# PCB_Design.net
KiCad netlist of a schematic drawn in EAGLE
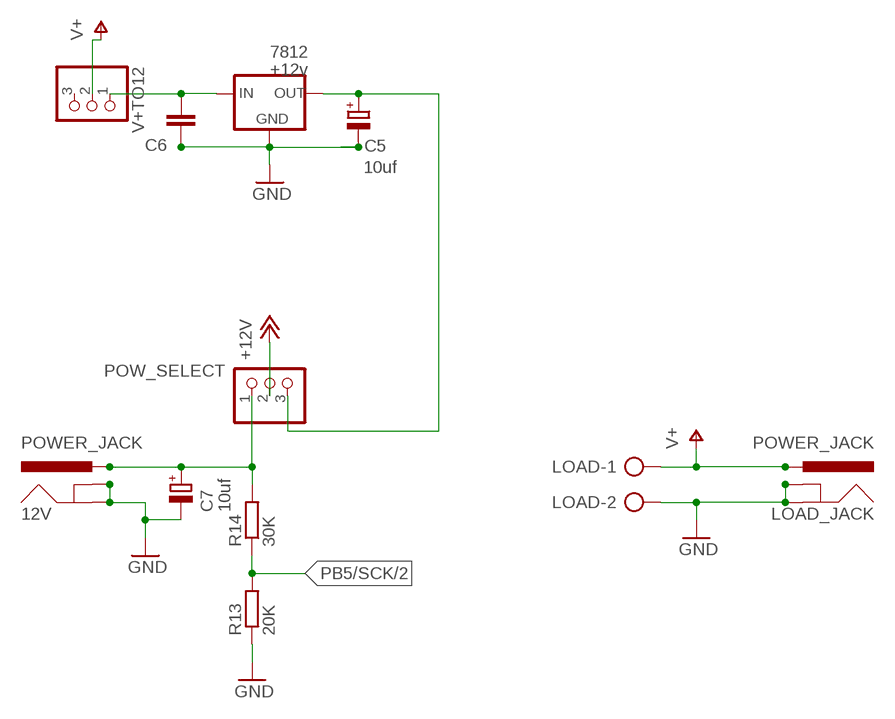
[diagram p0: schematic, sheet 1]
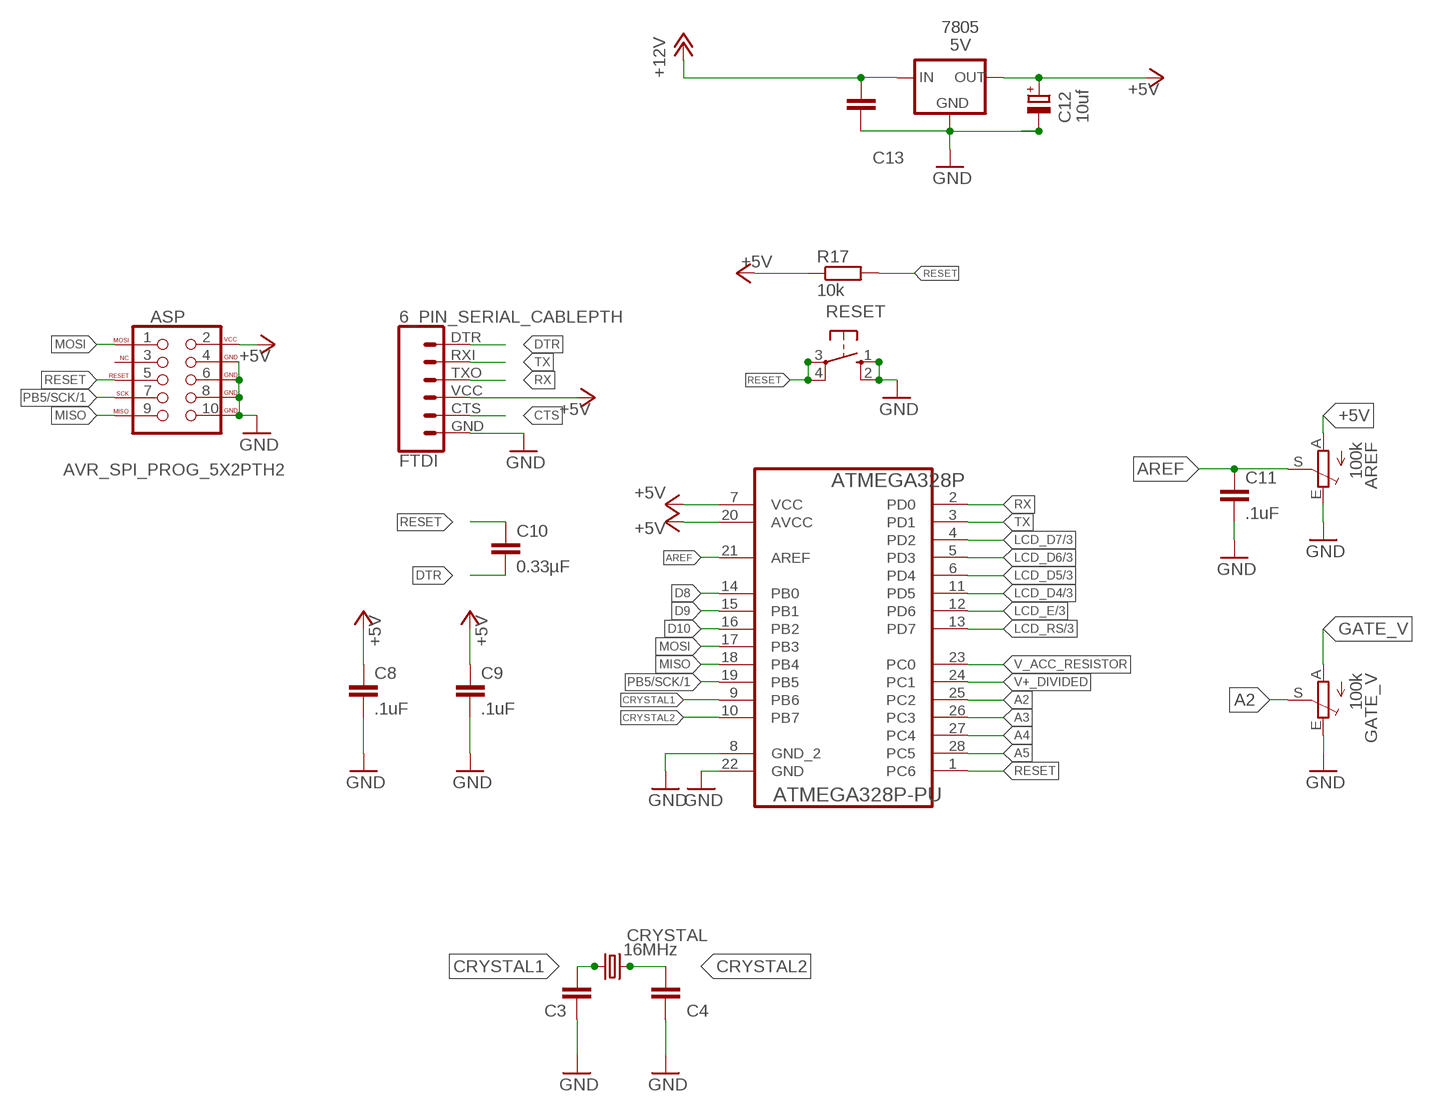
[diagram p1: schematic, sheet 2]
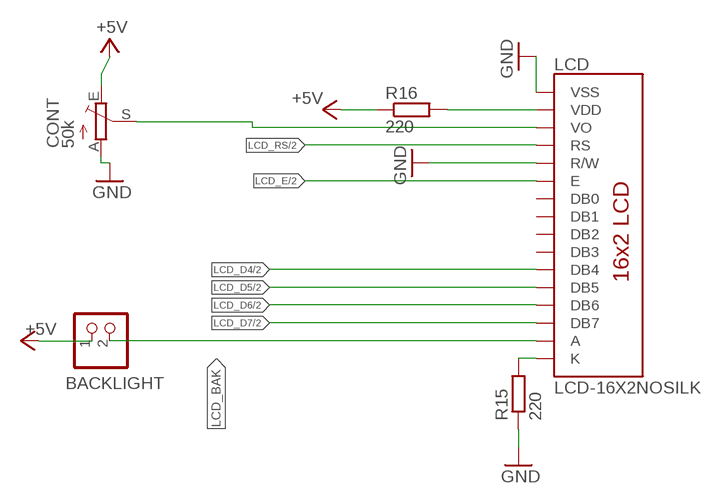
[diagram p2: schematic, sheet 3]

(export (version "E")
  (design (tool "Eeschema 10.0.6"))
  (components
    (comp (ref "12V")
      (value "POWER_JACK")
      (footprint "eagle-import:POWER_JACK_PTH")
      (libsource (lib "eagle-import") (part "POWER_JACK"))
    )
    (comp (ref "7812")
      (value "+12v")
      (footprint "eagle-import:TO-252")
      (libsource (lib "eagle-import") (part "V_REG_78XX7812"))
    )
    (comp (ref "C5")
      (value "10uf")
      (footprint "eagle-import:E2,5-6")
      (libsource (lib "eagle-import") (part "CPOL-EUE2.5-6"))
    )
    (comp (ref "C6")
      (value ".1uF")
      (footprint "eagle-import:C0805K")
      (libsource (lib "eagle-import") (part "C-EUC0805K"))
    )
    (comp (ref "C7")
      (value "10uf")
      (footprint "eagle-import:E2,5-6")
      (libsource (lib "eagle-import") (part "CPOL-EUE2.5-6"))
    )
    (comp (ref "LOAD")
      (value "AK500/2-H")
      (footprint "eagle-import:AK500_2-H")
      (libsource (lib "eagle-import") (part "AK500/2-H"))
    )
    (comp (ref "LOAD_JACK")
      (value "POWER_JACK")
      (footprint "eagle-import:POWER_JACK_PTH")
      (libsource (lib "eagle-import") (part "POWER_JACK"))
    )
    (comp (ref "POW_SELECT")
      (value "PINHD-1X3")
      (footprint "eagle-import:1X03")
      (libsource (lib "eagle-import") (part "PINHD-1X3"))
    )
    (comp (ref "R13")
      (value "20K")
      (footprint "eagle-import:M0805")
      (libsource (lib "eagle-import") (part "R-EU_M0805"))
    )
    (comp (ref "R14")
      (value "30K")
      (footprint "eagle-import:M0805")
      (libsource (lib "eagle-import") (part "R-EU_M0805"))
    )
    (comp (ref "V+TO12")
      (value "PINHD-1X3")
      (footprint "eagle-import:1X03")
      (libsource (lib "eagle-import") (part "pinhead_325_PINHD-1X3"))
    )
    (comp (ref "7805")
      (value "5V")
      (footprint "eagle-import:TO-252")
      (libsource (lib "eagle-import") (part "V_REG_78XX7812"))
    )
    (comp (ref "AREF")
      (value "100k")
      (footprint "eagle-import:S64W")
      (libsource (lib "eagle-import") (part "TRIM_EU-S64W"))
    )
    (comp (ref "ASP")
      (value "AVR_SPI_PROG_5X2PTH2")
      (footprint "eagle-import:2X5-SHROUDED")
      (libsource (lib "eagle-import") (part "AVR_SPI_PROG_5X2PTH2"))
    )
    (comp (ref "ATMEGA328P")
      (value "ATMEGA328P-PU")
      (footprint "eagle-import:DIP254P762X457-28")
      (libsource (lib "eagle-import") (part "ATMEGA328P-PU"))
    )
    (comp (ref "C3")
      (value "22pF")
      (footprint "eagle-import:C0805K")
      (libsource (lib "eagle-import") (part "C-EUC0805K"))
    )
    (comp (ref "C4")
      (value "22pF")
      (footprint "eagle-import:C0805K")
      (libsource (lib "eagle-import") (part "C-EUC0805K"))
    )
    (comp (ref "C8")
      (value ".1uF")
      (footprint "eagle-import:C0805K")
      (libsource (lib "eagle-import") (part "C-EUC0805K"))
    )
    (comp (ref "C9")
      (value ".1uF")
      (footprint "eagle-import:C0805K")
      (libsource (lib "eagle-import") (part "C-EUC0805K"))
    )
    (comp (ref "C10")
      (value "0.33µF")
      (footprint "eagle-import:C0805K")
      (libsource (lib "eagle-import") (part "C-EUC0805K"))
    )
    (comp (ref "C11")
      (value ".1uF")
      (footprint "eagle-import:C0805K")
      (libsource (lib "eagle-import") (part "C-EUC0805K"))
    )
    (comp (ref "C12")
      (value "10uf")
      (footprint "eagle-import:E2,5-6")
      (libsource (lib "eagle-import") (part "CPOL-EUE2.5-6"))
    )
    (comp (ref "C13")
      (value ".1uf")
      (footprint "eagle-import:C0805K")
      (libsource (lib "eagle-import") (part "C-EUC0805K"))
    )
    (comp (ref "CRYSTAL")
      (value "16MHz")
      (footprint "eagle-import:HC49U70")
      (libsource (lib "eagle-import") (part "CRYSTALHC49U70"))
    )
    (comp (ref "FTDI")
      (value "6_PIN_SERIAL_CABLEPTH")
      (footprint "eagle-import:FTDI_BASIC")
      (libsource (lib "eagle-import") (part "6_PIN_SERIAL_CABLEPTH"))
    )
    (comp (ref "GATE_V")
      (value "100k")
      (footprint "eagle-import:S64W")
      (libsource (lib "eagle-import") (part "TRIM_EU-S64W"))
    )
    (comp (ref "R17")
      (value "10k")
      (footprint "eagle-import:M0805")
      (libsource (lib "eagle-import") (part "R-EU_M0805"))
    )
    (comp (ref "RESET")
      (value "10-XX")
      (footprint "eagle-import:B3F-10XX")
      (fields (field (name "MPN") "B3F-1000"))
      (libsource (lib "eagle-import") (part "10-XX"))
    )
    (comp (ref "BACKLIGHT")
      (value "PINHD-1X2")
      (footprint "eagle-import:1X02")
      (libsource (lib "eagle-import") (part "PINHD-1X2"))
    )
    (comp (ref "CONT")
      (value "50k")
      (footprint "eagle-import:S64W")
      (libsource (lib "eagle-import") (part "TRIM_EU-S64W"))
    )
    (comp (ref "LCD")
      (value "LCD-16X2NOSILK")
      (footprint "eagle-import:LCD-16X2_NOSILK")
      (libsource (lib "eagle-import") (part "LCD-16X2NOSILK"))
    )
    (comp (ref "R15")
      (value "220")
      (footprint "eagle-import:M0805")
      (libsource (lib "eagle-import") (part "R-EU_M0805"))
    )
    (comp (ref "R16")
      (value "220")
      (footprint "eagle-import:M0805")
      (libsource (lib "eagle-import") (part "R-EU_M0805"))
    )
  )
  (nets
    (net (code "1") (name "+5V") (class "Default")
      (node (ref "7805") (pin "2") (pinfunction "OUT_2") (pintype "passive"))
      (node (ref "AREF") (pin "A") (pinfunction "A_A") (pintype "passive"))
      (node (ref "ASP") (pin "2") (pinfunction "VCC_2") (pintype "power_in"))
      (node (ref "ATMEGA328P") (pin "20") (pinfunction "AVCC_20") (pintype "power_in"))
      (node (ref "ATMEGA328P") (pin "7") (pinfunction "VCC_7") (pintype "power_in"))
      (node (ref "BACKLIGHT") (pin "1") (pinfunction "1_1") (pintype "passive"))
      (node (ref "C12") (pin "+") (pinfunction "+_+") (pintype "passive"))
      (node (ref "C8") (pin "1") (pinfunction "1_1") (pintype "passive"))
      (node (ref "C9") (pin "1") (pinfunction "1_1") (pintype "passive"))
      (node (ref "CONT") (pin "E") (pinfunction "E_E") (pintype "passive"))
      (node (ref "FTDI") (pin "VCC") (pinfunction "4_VCC") (pintype "passive"))
      (node (ref "R16") (pin "1") (pinfunction "1_1") (pintype "passive"))
      (node (ref "R17") (pin "1") (pinfunction "1_1") (pintype "passive"))
    )
    (net (code "2") (name "+12V") (class "Default")
      (node (ref "7805") (pin "1") (pinfunction "IN_1") (pintype "input"))
      (node (ref "C13") (pin "1") (pinfunction "1_1") (pintype "passive"))
      (node (ref "POW_SELECT") (pin "2") (pinfunction "2_2") (pintype "passive"))
    )
    (net (code "3") (name "A2") (class "Default")
      (node (ref "ATMEGA328P") (pin "25") (pinfunction "PC2_25") (pintype "bidirectional"))
      (node (ref "GATE_V") (pin "S") (pinfunction "S_S") (pintype "passive"))
    )
    (net (code "4") (name "A3") (class "Default")
      (node (ref "ATMEGA328P") (pin "26") (pinfunction "PC3_26") (pintype "bidirectional"))
    )
    (net (code "5") (name "A4") (class "Default")
      (node (ref "ATMEGA328P") (pin "27") (pinfunction "PC4_27") (pintype "bidirectional"))
    )
    (net (code "6") (name "A5") (class "Default")
      (node (ref "ATMEGA328P") (pin "28") (pinfunction "PC5_28") (pintype "bidirectional"))
    )
    (net (code "7") (name "AREF") (class "Default")
      (node (ref "AREF") (pin "S") (pinfunction "S_S") (pintype "passive"))
      (node (ref "ATMEGA328P") (pin "21") (pinfunction "AREF_21") (pintype "input"))
      (node (ref "C11") (pin "1") (pinfunction "1_1") (pintype "passive"))
    )
    (net (code "8") (name "CRYSTAL1") (class "Default")
      (node (ref "ATMEGA328P") (pin "9") (pinfunction "PB6_9") (pintype "bidirectional"))
      (node (ref "C3") (pin "2") (pinfunction "2_2") (pintype "passive"))
      (node (ref "CRYSTAL") (pin "1") (pinfunction "1_1") (pintype "passive"))
    )
    (net (code "9") (name "CRYSTAL2") (class "Default")
      (node (ref "ATMEGA328P") (pin "10") (pinfunction "PB7_10") (pintype "bidirectional"))
      (node (ref "C4") (pin "2") (pinfunction "2_2") (pintype "passive"))
      (node (ref "CRYSTAL") (pin "2") (pinfunction "2_2") (pintype "passive"))
    )
    (net (code "10") (name "CTS") (class "Default")
      (node (ref "FTDI") (pin "CTS") (pinfunction "5_CTS") (pintype "passive"))
    )
    (net (code "11") (name "D8") (class "Default")
      (node (ref "ATMEGA328P") (pin "14") (pinfunction "PB0_14") (pintype "bidirectional"))
    )
    (net (code "12") (name "D9") (class "Default")
      (node (ref "ATMEGA328P") (pin "15") (pinfunction "PB1_15") (pintype "bidirectional"))
    )
    (net (code "13") (name "D10") (class "Default")
      (node (ref "ATMEGA328P") (pin "16") (pinfunction "PB2_16") (pintype "bidirectional"))
    )
    (net (code "14") (name "DTR") (class "Default")
      (node (ref "C10") (pin "2") (pinfunction "2_2") (pintype "passive"))
      (node (ref "FTDI") (pin "DTR") (pinfunction "1_DTR") (pintype "passive"))
    )
    (net (code "15") (name "GATE_V") (class "Default")
      (node (ref "GATE_V") (pin "A") (pinfunction "A_A") (pintype "passive"))
    )
    (net (code "16") (name "GND") (class "Default")
      (node (ref "12V") (pin "GND") (pinfunction "GND_GND") (pintype "bidirectional"))
      (node (ref "12V") (pin "GNDBREAK") (pinfunction "GNDBREAK_GNDBREAK") (pintype "bidirectional"))
      (node (ref "7805") (pin "3") (pinfunction "GND_3") (pintype "input"))
      (node (ref "7812") (pin "3") (pinfunction "GND_3") (pintype "input"))
      (node (ref "AREF") (pin "E") (pinfunction "E_E") (pintype "passive"))
      (node (ref "ASP") (pin "10") (pinfunction "GND_10") (pintype "power_in"))
      (node (ref "ASP") (pin "4") (pinfunction "GND_4") (pintype "power_in"))
      (node (ref "ASP") (pin "6") (pinfunction "GND_6") (pintype "power_in"))
      (node (ref "ASP") (pin "8") (pinfunction "GND_8") (pintype "power_in"))
      (node (ref "ATMEGA328P") (pin "22") (pinfunction "GND_22") (pintype "passive"))
      (node (ref "ATMEGA328P") (pin "8") (pinfunction "GND_2_8") (pintype "passive"))
      (node (ref "C11") (pin "2") (pinfunction "2_2") (pintype "passive"))
      (node (ref "C12") (pin "-") (pinfunction "-_-") (pintype "passive"))
      (node (ref "C13") (pin "2") (pinfunction "2_2") (pintype "passive"))
      (node (ref "C3") (pin "1") (pinfunction "1_1") (pintype "passive"))
      (node (ref "C4") (pin "1") (pinfunction "1_1") (pintype "passive"))
      (node (ref "C5") (pin "-") (pinfunction "-_-") (pintype "passive"))
      (node (ref "C6") (pin "2") (pinfunction "2_2") (pintype "passive"))
      (node (ref "C7") (pin "-") (pinfunction "-_-") (pintype "passive"))
      (node (ref "C8") (pin "2") (pinfunction "2_2") (pintype "passive"))
      (node (ref "C9") (pin "2") (pinfunction "2_2") (pintype "passive"))
      (node (ref "CONT") (pin "A") (pinfunction "A_A") (pintype "passive"))
      (node (ref "FTDI") (pin "GND") (pinfunction "6_GND") (pintype "passive"))
      (node (ref "GATE_V") (pin "E") (pinfunction "E_E") (pintype "passive"))
      (node (ref "LCD") (pin "1") (pinfunction "VSS_1") (pintype "power_in"))
      (node (ref "LCD") (pin "5") (pinfunction "R/W_5") (pintype "input"))
      (node (ref "LOAD") (pin "2") (pinfunction "KL_2") (pintype "passive"))
      (node (ref "LOAD_JACK") (pin "GND") (pinfunction "GND_GND") (pintype "bidirectional"))
      (node (ref "LOAD_JACK") (pin "GNDBREAK") (pinfunction "GNDBREAK_GNDBREAK") (pintype "bidirectional"))
      (node (ref "R13") (pin "1") (pinfunction "1_1") (pintype "passive"))
      (node (ref "R15") (pin "1") (pinfunction "1_1") (pintype "passive"))
      (node (ref "RESET") (pin "1") (pinfunction "S_1") (pintype "passive"))
      (node (ref "RESET") (pin "2") (pinfunction "S1_2") (pintype "passive"))
    )
    (net (code "17") (name "LCD_BAK") (class "Default")
      (node (ref "BACKLIGHT") (pin "2") (pinfunction "2_2") (pintype "passive"))
      (node (ref "LCD") (pin "15") (pinfunction "A_15") (pintype "power_in"))
    )
    (net (code "18") (name "LCD_D4") (class "Default")
      (node (ref "ATMEGA328P") (pin "11") (pinfunction "PD5_11") (pintype "bidirectional"))
      (node (ref "LCD") (pin "11") (pinfunction "DB4_11") (pintype "bidirectional"))
    )
    (net (code "19") (name "LCD_D5") (class "Default")
      (node (ref "ATMEGA328P") (pin "6") (pinfunction "PD4_6") (pintype "bidirectional"))
      (node (ref "LCD") (pin "12") (pinfunction "DB5_12") (pintype "bidirectional"))
    )
    (net (code "20") (name "LCD_D6") (class "Default")
      (node (ref "ATMEGA328P") (pin "5") (pinfunction "PD3_5") (pintype "bidirectional"))
      (node (ref "LCD") (pin "13") (pinfunction "DB6_13") (pintype "bidirectional"))
    )
    (net (code "21") (name "LCD_D7") (class "Default")
      (node (ref "ATMEGA328P") (pin "4") (pinfunction "PD2_4") (pintype "bidirectional"))
      (node (ref "LCD") (pin "14") (pinfunction "DB7_14") (pintype "bidirectional"))
    )
    (net (code "22") (name "LCD_E") (class "Default")
      (node (ref "ATMEGA328P") (pin "12") (pinfunction "PD6_12") (pintype "bidirectional"))
      (node (ref "LCD") (pin "6") (pinfunction "E_6") (pintype "input"))
    )
    (net (code "23") (name "LCD_RS") (class "Default")
      (node (ref "ATMEGA328P") (pin "13") (pinfunction "PD7_13") (pintype "bidirectional"))
      (node (ref "LCD") (pin "4") (pinfunction "RS_4") (pintype "input"))
    )
    (net (code "24") (name "MISO") (class "Default")
      (node (ref "ASP") (pin "9") (pinfunction "MISO_9") (pintype "passive"))
      (node (ref "ATMEGA328P") (pin "18") (pinfunction "PB4_18") (pintype "bidirectional"))
    )
    (net (code "25") (name "MOSI") (class "Default")
      (node (ref "ASP") (pin "1") (pinfunction "MOSI_1") (pintype "passive"))
      (node (ref "ATMEGA328P") (pin "17") (pinfunction "PB3_17") (pintype "bidirectional"))
    )
    (net (code "26") (name "Net-(12V-PadPWR)") (class "Default")
      (node (ref "12V") (pin "PWR") (pinfunction "PWR_PWR") (pintype "bidirectional"))
      (node (ref "C7") (pin "+") (pinfunction "+_+") (pintype "passive"))
      (node (ref "POW_SELECT") (pin "1") (pinfunction "1_1") (pintype "passive"))
      (node (ref "R14") (pin "2") (pinfunction "2_2") (pintype "passive"))
    )
    (net (code "27") (name "Net-(7812-IN)") (class "Default")
      (node (ref "7812") (pin "1") (pinfunction "IN_1") (pintype "input"))
      (node (ref "C6") (pin "1") (pinfunction "1_1") (pintype "passive"))
      (node (ref "V+TO12") (pin "1") (pinfunction "1_1") (pintype "passive"))
    )
    (net (code "28") (name "Net-(7812-OUT)") (class "Default")
      (node (ref "7812") (pin "2") (pinfunction "OUT_2") (pintype "passive"))
      (node (ref "C5") (pin "+") (pinfunction "+_+") (pintype "passive"))
      (node (ref "POW_SELECT") (pin "3") (pinfunction "3_3") (pintype "passive"))
    )
    (net (code "29") (name "Net-(LCD-K)") (class "Default")
      (node (ref "LCD") (pin "16") (pinfunction "K_16") (pintype "power_in"))
      (node (ref "R15") (pin "2") (pinfunction "2_2") (pintype "passive"))
    )
    (net (code "30") (name "Net-(LCD-VDD)") (class "Default")
      (node (ref "LCD") (pin "2") (pinfunction "VDD_2") (pintype "power_in"))
      (node (ref "R16") (pin "2") (pinfunction "2_2") (pintype "passive"))
    )
    (net (code "31") (name "Net-(LCD-VO)") (class "Default")
      (node (ref "CONT") (pin "S") (pinfunction "S_S") (pintype "passive"))
      (node (ref "LCD") (pin "3") (pinfunction "VO_3") (pintype "bidirectional"))
    )
    (net (code "32") (name "PB5{slash}SCK") (class "Default")
      (node (ref "ASP") (pin "7") (pinfunction "SCK_7") (pintype "passive"))
      (node (ref "ATMEGA328P") (pin "19") (pinfunction "PB5_19") (pintype "bidirectional"))
      (node (ref "R13") (pin "2") (pinfunction "2_2") (pintype "passive"))
      (node (ref "R14") (pin "1") (pinfunction "1_1") (pintype "passive"))
    )
    (net (code "33") (name "RESET") (class "Default")
      (node (ref "ASP") (pin "5") (pinfunction "RESET_5") (pintype "passive"))
      (node (ref "ATMEGA328P") (pin "1") (pinfunction "PC6_1") (pintype "bidirectional"))
      (node (ref "C10") (pin "1") (pinfunction "1_1") (pintype "passive"))
      (node (ref "R17") (pin "2") (pinfunction "2_2") (pintype "passive"))
      (node (ref "RESET") (pin "3") (pinfunction "P_3") (pintype "passive"))
      (node (ref "RESET") (pin "4") (pinfunction "P1_4") (pintype "passive"))
    )
    (net (code "34") (name "RX") (class "Default")
      (node (ref "ATMEGA328P") (pin "2") (pinfunction "PD0_2") (pintype "bidirectional"))
      (node (ref "FTDI") (pin "TXO") (pinfunction "3_TXO") (pintype "passive"))
    )
    (net (code "35") (name "TX") (class "Default")
      (node (ref "ATMEGA328P") (pin "3") (pinfunction "PD1_3") (pintype "bidirectional"))
      (node (ref "FTDI") (pin "RXI") (pinfunction "2_RXI") (pintype "passive"))
    )
    (net (code "36") (name "V+") (class "Default")
      (node (ref "LOAD") (pin "1") (pinfunction "KL_1") (pintype "passive"))
      (node (ref "LOAD_JACK") (pin "PWR") (pinfunction "PWR_PWR") (pintype "bidirectional"))
      (node (ref "V+TO12") (pin "2") (pinfunction "2_2") (pintype "passive"))
    )
    (net (code "37") (name "V+_DIVIDED") (class "Default")
      (node (ref "ATMEGA328P") (pin "24") (pinfunction "PC1_24") (pintype "bidirectional"))
    )
    (net (code "38") (name "V_ACC_RESISTOR") (class "Default")
      (node (ref "ATMEGA328P") (pin "23") (pinfunction "PC0_23") (pintype "bidirectional"))
    )
    (net (code "39") (name "unconnected-(ASP-NC-Pad3)") (class "Default")
      (node (ref "ASP") (pin "3") (pinfunction "NC_3") (pintype "no_connect"))
    )
    (net (code "40") (name "unconnected-(LCD-DB0-Pad7)") (class "Default")
      (node (ref "LCD") (pin "7") (pinfunction "DB0_7") (pintype "bidirectional"))
    )
    (net (code "41") (name "unconnected-(LCD-DB1-Pad8)") (class "Default")
      (node (ref "LCD") (pin "8") (pinfunction "DB1_8") (pintype "bidirectional"))
    )
    (net (code "42") (name "unconnected-(LCD-DB2-Pad9)") (class "Default")
      (node (ref "LCD") (pin "9") (pinfunction "DB2_9") (pintype "bidirectional"))
    )
    (net (code "43") (name "unconnected-(LCD-DB3-Pad10)") (class "Default")
      (node (ref "LCD") (pin "10") (pinfunction "DB3_10") (pintype "bidirectional"))
    )
    (net (code "44") (name "unconnected-(V+TO12-Pad3)") (class "Default")
      (node (ref "V+TO12") (pin "3") (pinfunction "3_3") (pintype "passive"))
    )
  )
)
